# STM32_MCU.net
KiCad netlist of a schematic drawn in Altium Designer
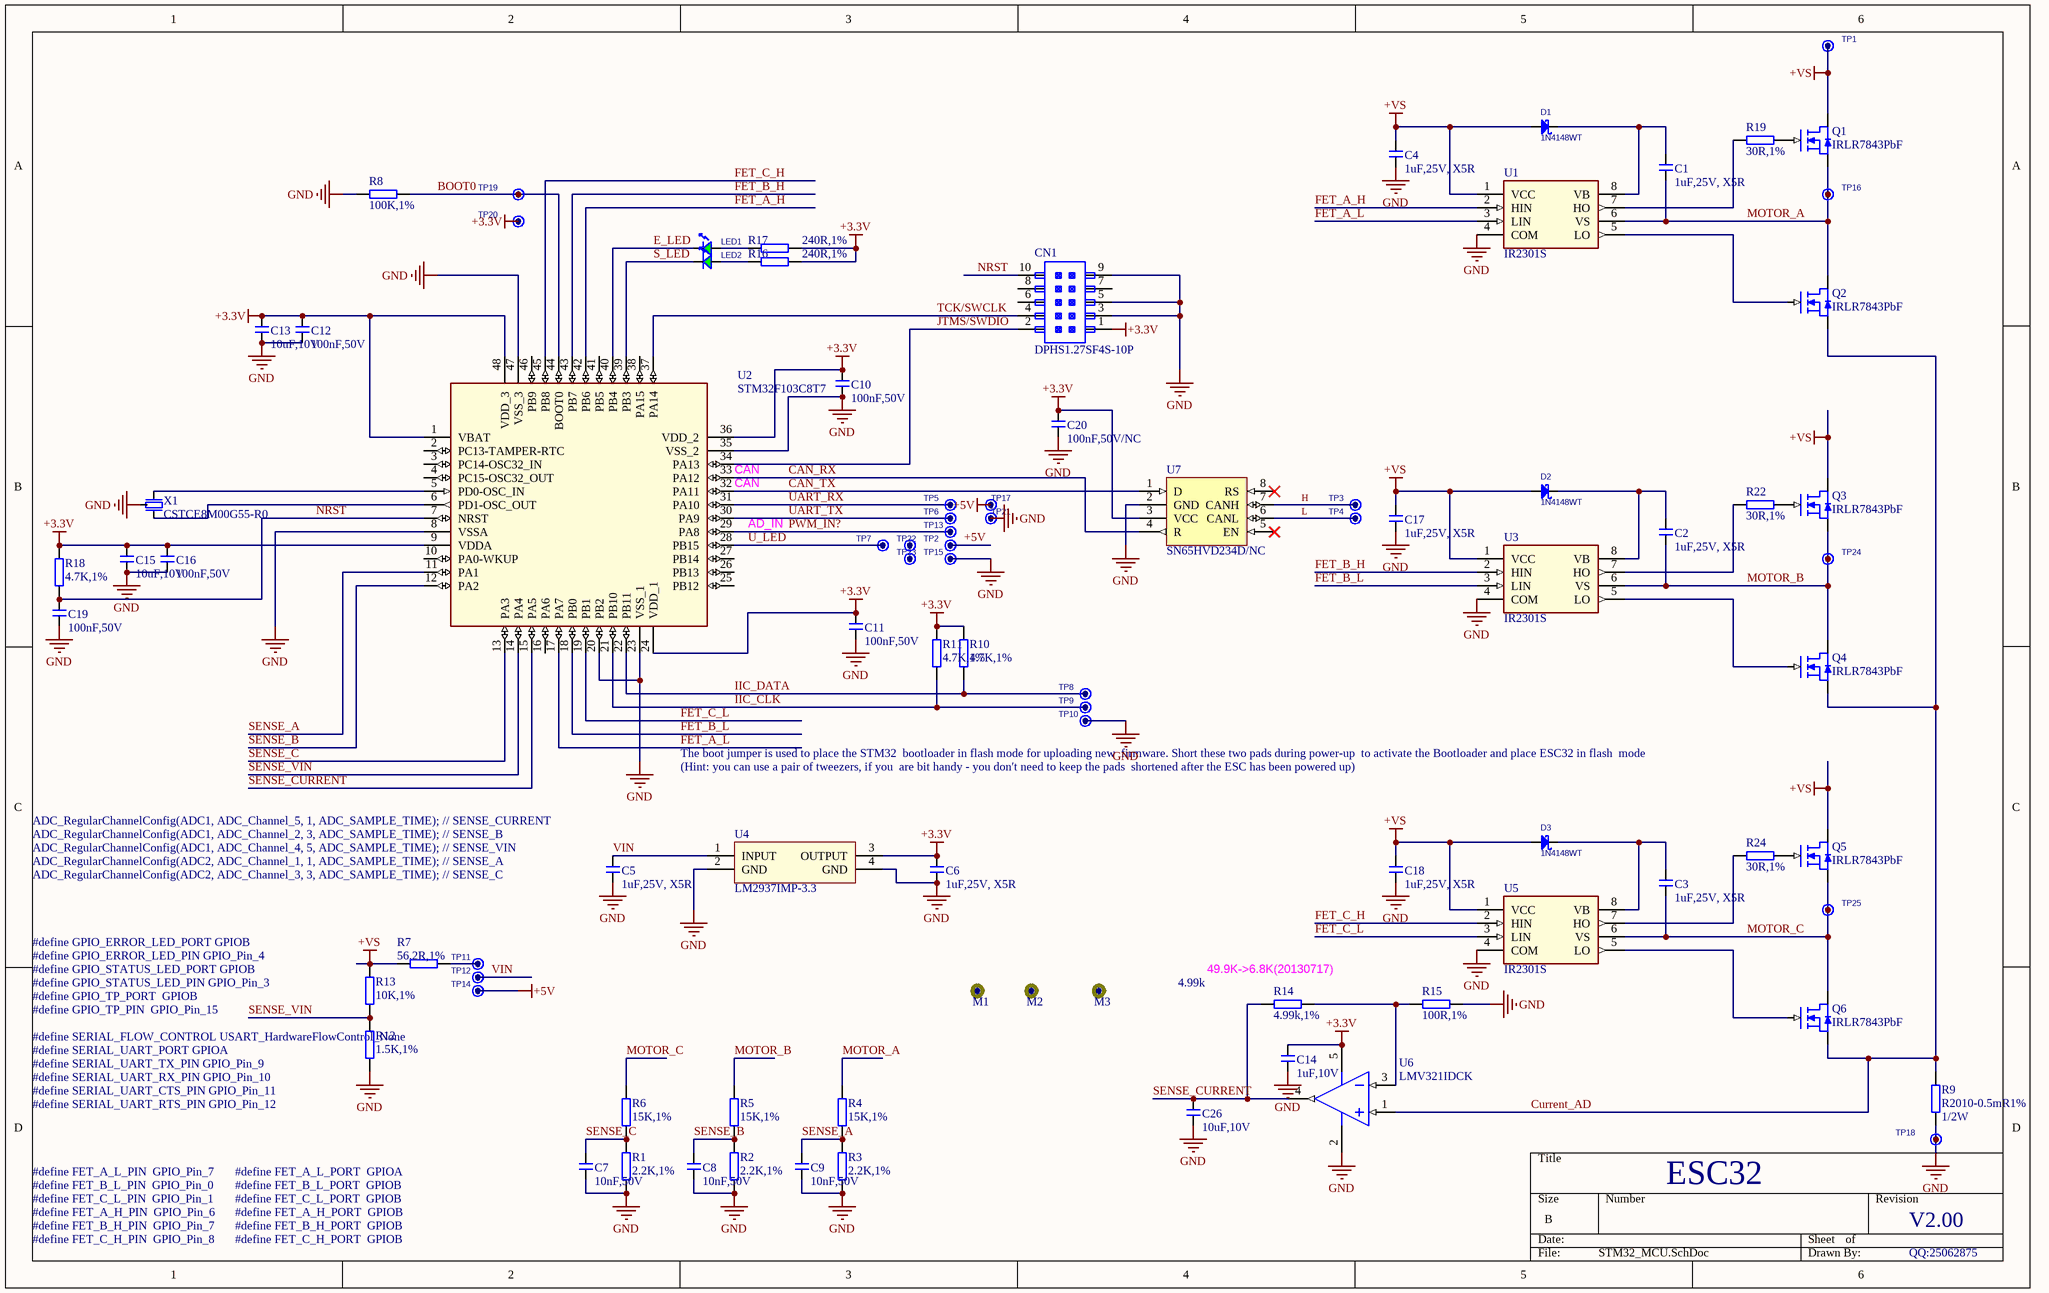
[diagram p0: STM32_MCU.SchDoc]

(export (version "E")
  (design (tool "Eeschema 10.0.6"))
  (components
    (comp (ref "C1")
      (value "1uF,25V, X5R")
      (footprint "CAPC2012L")
      (description "X5R,20%")
      (fields (field (name "Comment") "C0805-1uF/25V"))
      (libsource (lib "cap_n") (part "C0805-1uF/25V"))
    )
    (comp (ref "C2")
      (value "1uF,25V, X5R")
      (footprint "CAPC2012L")
      (description "X5R,20%")
      (fields (field (name "Comment") "C0805-1uF/25V"))
      (libsource (lib "cap_n") (part "C0805-1uF/25V"))
    )
    (comp (ref "C3")
      (value "1uF,25V, X5R")
      (footprint "CAPC2012L")
      (description "X5R,20%")
      (fields (field (name "Comment") "C0805-1uF/25V"))
      (libsource (lib "cap_n") (part "C0805-1uF/25V"))
    )
    (comp (ref "C4")
      (value "1uF,25V, X5R")
      (footprint "CAPC2012L")
      (description "X5R,20%")
      (fields (field (name "Comment") "C0805-1uF/25V"))
      (libsource (lib "cap_n") (part "C0805-1uF/25V"))
    )
    (comp (ref "C5")
      (value "1uF,25V, X5R")
      (footprint "CAPC2012L")
      (description "X5R,20%")
      (fields (field (name "Comment") "C0805-1uF/25V"))
      (libsource (lib "cap_n") (part "C0805-1uF/25V"))
    )
    (comp (ref "C6")
      (value "1uF,25V, X5R")
      (footprint "CAPC2012L")
      (description "X5R,20%")
      (fields (field (name "Comment") "C0805-1uF/25V"))
      (libsource (lib "cap_n") (part "C0805-1uF/25V"))
    )
    (comp (ref "C7")
      (value "10nF,50V")
      (footprint "CAPC1608L")
      (description "X7R")
      (fields (field (name "Comment") "C0603-10nF/50V"))
      (libsource (lib "cap_n") (part "C0603-100nF/50V"))
    )
    (comp (ref "C8")
      (value "10nF,50V")
      (footprint "CAPC1608L")
      (description "X7R")
      (fields (field (name "Comment") "C0603-10nF/50V"))
      (libsource (lib "cap_n") (part "C0603-100nF/50V"))
    )
    (comp (ref "C9")
      (value "10nF,50V")
      (footprint "CAPC1608L")
      (description "X7R")
      (fields (field (name "Comment") "C0603-10nF/50V"))
      (libsource (lib "cap_n") (part "C0603-100nF/50V"))
    )
    (comp (ref "C10")
      (value "100nF,50V")
      (footprint "CAPC1608L")
      (description "X7R")
      (fields (field (name "Comment") "C0603-100nF/50V"))
      (libsource (lib "cap_n") (part "C0603-100nF/50V"))
    )
    (comp (ref "C11")
      (value "100nF,50V")
      (footprint "CAPC1608L")
      (description "X7R")
      (fields (field (name "Comment") "C0603-100nF/50V"))
      (libsource (lib "cap_n") (part "C0603-100nF/50V"))
    )
    (comp (ref "C12")
      (value "100nF,50V")
      (footprint "CAPC1608L")
      (description "X7R")
      (fields (field (name "Comment") "C0603-100nF/50V"))
      (libsource (lib "cap_n") (part "C0603-100nF/50V"))
    )
    (comp (ref "C13")
      (value "10uF,10V")
      (footprint "CAPC1608L")
      (description "X5R,20%")
      (fields (field (name "Comment") "C0603-10uF/10V"))
      (libsource (lib "cap_n") (part "C0603-10uF/10V"))
    )
    (comp (ref "C14")
      (value "1uF,10V")
      (footprint "CAPC1608L")
      (description "X5R,20%")
      (fields (field (name "Comment") "C0603-1uF/10V"))
      (libsource (lib "cap_n") (part "C0603-1uF/10V"))
    )
    (comp (ref "C15")
      (value "10uF,10V")
      (footprint "CAPC1608L")
      (description "X5R,20%")
      (fields (field (name "Comment") "C0603-10uF/10V"))
      (libsource (lib "cap_n") (part "C0603-10uF/10V"))
    )
    (comp (ref "C16")
      (value "100nF,50V")
      (footprint "CAPC1608L")
      (description "X7R")
      (fields (field (name "Comment") "C0603-100nF/50V"))
      (libsource (lib "cap_n") (part "C0603-100nF/50V"))
    )
    (comp (ref "C17")
      (value "1uF,25V, X5R")
      (footprint "CAPC2012L")
      (description "X5R,20%")
      (fields (field (name "Comment") "C0805-1uF/25V"))
      (libsource (lib "cap_n") (part "C0805-1uF/25V"))
    )
    (comp (ref "C18")
      (value "1uF,25V, X5R")
      (footprint "CAPC2012L")
      (description "X5R,20%")
      (fields (field (name "Comment") "C0805-1uF/25V"))
      (libsource (lib "cap_n") (part "C0805-1uF/25V"))
    )
    (comp (ref "C19")
      (value "100nF,50V")
      (footprint "CAPC1608L")
      (description "X7R")
      (fields (field (name "Comment") "C0603-100nF/50V"))
      (libsource (lib "cap_n") (part "C0603-100nF/50V"))
    )
    (comp (ref "C20")
      (value "100nF,50V/NC")
      (footprint "CAPC1608L")
      (description "X7R")
      (fields (field (name "Comment") "C0603-100nF/50V/NC"))
      (libsource (lib "cap_n") (part "C0603-100nF/50V"))
    )
    (comp (ref "C26")
      (value "10uF,10V")
      (footprint "CAPC1608L")
      (description "X7R")
      (fields (field (name "Comment") "C0603-10uF/10V"))
      (libsource (lib "cap_n") (part "C0603-100nF/50V"))
    )
    (comp (ref "CN1")
      (value "DPHS1.27SF4S-10P")
      (footprint "DPHS1.27SF4S-10P")
      (description "1.27 间距表贴双排针, 40芯, PCB板高度为4.3mm")
      (libsource (lib "Connector_STD") (part "DPHS1.27SF4S-10P"))
    )
    (comp (ref "D1")
      (value "1N4148WT")
      (footprint "DIOM1608X06N")
      (description "SURFACE MOUNT FAST SWITCHING DIODE")
      (fields (field (name "MFR") "DIODES"))
      (libsource (lib "Diode_STD") (part "1N4148WT"))
    )
    (comp (ref "D2")
      (value "1N4148WT")
      (footprint "DIOM1608X06N")
      (description "SURFACE MOUNT FAST SWITCHING DIODE")
      (fields (field (name "MFR") "DIODES"))
      (libsource (lib "Diode_STD") (part "1N4148WT"))
    )
    (comp (ref "D3")
      (value "1N4148WT")
      (footprint "DIOM1608X06N")
      (description "SURFACE MOUNT FAST SWITCHING DIODE")
      (fields (field (name "MFR") "DIODES"))
      (libsource (lib "Diode_STD") (part "1N4148WT"))
    )
    (comp (ref "LED1")
      (value "LED-R0603")
      (footprint "LED-G0603")
      (description "LED发光二极管, 绿色, 0603封装")
      (libsource (lib "LEDtube_STD") (part "LED-G0603"))
    )
    (comp (ref "LED2")
      (value "LED-G0603")
      (footprint "LED-G0603")
      (description "LED发光二极管, 绿色, 0603封装")
      (libsource (lib "LEDtube_STD") (part "LED-G0603"))
    )
    (comp (ref "M1")
      (value "MarkPad")
      (footprint "MarkPad")
      (description "mark, 标记芯片和板边位置")
      (libsource (lib "Miscellaneous_STD") (part "MarkPad"))
    )
    (comp (ref "M2")
      (value "MarkPad")
      (footprint "MarkPad")
      (description "mark, 标记芯片和板边位置")
      (libsource (lib "Miscellaneous_STD") (part "MarkPad"))
    )
    (comp (ref "M3")
      (value "MarkPad")
      (footprint "MarkPad")
      (description "mark, 标记芯片和板边位置")
      (libsource (lib "Miscellaneous_STD") (part "MarkPad"))
    )
    (comp (ref "Q1")
      (value "IRLR7843PbF")
      (footprint "TO230P990X239-3N")
      (libsource (lib "MOSFET_STD") (part "IRLR7843PbF"))
    )
    (comp (ref "Q2")
      (value "IRLR7843PbF")
      (footprint "TO230P990X239-3N")
      (libsource (lib "MOSFET_STD") (part "IRLR7843PbF"))
    )
    (comp (ref "Q3")
      (value "IRLR7843PbF")
      (footprint "TO230P990X239-3N")
      (libsource (lib "MOSFET_STD") (part "IRLR7843PbF"))
    )
    (comp (ref "Q4")
      (value "IRLR7843PbF")
      (footprint "TO230P990X239-3N")
      (libsource (lib "MOSFET_STD") (part "IRLR7843PbF"))
    )
    (comp (ref "Q5")
      (value "IRLR7843PbF")
      (footprint "TO230P990X239-3N")
      (libsource (lib "MOSFET_STD") (part "IRLR7843PbF"))
    )
    (comp (ref "Q6")
      (value "IRLR7843PbF")
      (footprint "TO230P990X239-3N")
      (libsource (lib "MOSFET_STD") (part "IRLR7843PbF"))
    )
    (comp (ref "R1")
      (value "2.2K,1%")
      (footprint "RESC1608L")
      (fields (field (name "TOLERANCE") "1%") (field (name "Comment") "R0603-2.2K"))
      (libsource (lib "res") (part "R0603-2.2K"))
    )
    (comp (ref "R2")
      (value "2.2K,1%")
      (footprint "RESC1608L")
      (fields (field (name "TOLERANCE") "1%") (field (name "Comment") "R0603-2.2K"))
      (libsource (lib "res") (part "R0603-2.2K"))
    )
    (comp (ref "R3")
      (value "2.2K,1%")
      (footprint "RESC1608L")
      (fields (field (name "TOLERANCE") "1%") (field (name "Comment") "R0603-2.2K"))
      (libsource (lib "res") (part "R0603-2.2K"))
    )
    (comp (ref "R4")
      (value "15K,1%")
      (footprint "RESC1608L")
      (description "10K,1%")
      (fields (field (name "TOLERANCE") "1%") (field (name "Comment") "R0603-15K"))
      (libsource (lib "res") (part "R0603-10K"))
    )
    (comp (ref "R5")
      (value "15K,1%")
      (footprint "RESC1608L")
      (description "10K,1%")
      (fields (field (name "TOLERANCE") "1%") (field (name "Comment") "R0603-15K"))
      (libsource (lib "res") (part "R0603-10K"))
    )
    (comp (ref "R6")
      (value "15K,1%")
      (footprint "RESC1608L")
      (description "10K,1%")
      (fields (field (name "TOLERANCE") "1%") (field (name "Comment") "R0603-15K"))
      (libsource (lib "res") (part "R0603-10K"))
    )
    (comp (ref "R7")
      (value "56.2R,1%")
      (footprint "RESC2012L")
      (fields (field (name "Comment") "R0805-56.2R"))
      (libsource (lib "res") (part "R0805-56.2R"))
    )
    (comp (ref "R8")
      (value "100K,1%")
      (footprint "RESC1608L")
      (fields (field (name "TOLERANCE") "1%") (field (name "Comment") "R0603-100K"))
      (libsource (lib "res") (part "R0603-100K"))
    )
    (comp (ref "R9")
      (value "R2010-0.5mR1%")
      (footprint "RC2010-5025X07N")
      (description "Vishay WSL功率型电阻")
      (fields (field (name "功?") "1/2W"))
      (libsource (lib "Resistance_STD") (part "R2010-0.22R1%"))
    )
    (comp (ref "R10")
      (value "4.7K,1%")
      (footprint "RESC1608L")
      (fields (field (name "TOLERANCE") "1%") (field (name "Comment") "R0603-4.7K"))
      (libsource (lib "res") (part "R0603-4.7K"))
    )
    (comp (ref "R11")
      (value "4.7K,1%")
      (footprint "RESC1608L")
      (fields (field (name "TOLERANCE") "1%") (field (name "Comment") "R0603-4.7K"))
      (libsource (lib "res") (part "R0603-4.7K"))
    )
    (comp (ref "R12")
      (value "1.5K,1%")
      (footprint "RESC1608L")
      (description "15K,1%")
      (fields (field (name "TOLERANCE") "1%") (field (name "Comment") "R0603-1.5K"))
      (libsource (lib "res") (part "R0603-15K"))
    )
    (comp (ref "R13")
      (value "10K,1%")
      (footprint "RESC1608L")
      (description "100K,1%")
      (fields (field (name "TOLERANCE") "1%") (field (name "Comment") "R0603-10K"))
      (libsource (lib "res") (part "R0603-100K"))
    )
    (comp (ref "R14")
      (value "4.99k,1%")
      (footprint "RESC1608L")
      (fields (field (name "TOLERANCE") "1%") (field (name "Comment") "R0603-4.99k"))
      (libsource (lib "res") (part "R0603-49.9K"))
    )
    (comp (ref "R15")
      (value "100R,1%")
      (footprint "RESC1608L")
      (fields (field (name "TOLERANCE") "1%") (field (name "Comment") "R0603-100R"))
      (libsource (lib "res") (part "R0603-100R"))
    )
    (comp (ref "R16")
      (value "240R,1%")
      (footprint "RESC1608L")
      (fields (field (name "TOLERANCE") "1%") (field (name "Comment") "R0603-240R"))
      (libsource (lib "res") (part "R0603-240R"))
    )
    (comp (ref "R17")
      (value "240R,1%")
      (footprint "RESC1608L")
      (fields (field (name "TOLERANCE") "1%") (field (name "Comment") "R0603-240R"))
      (libsource (lib "res") (part "R0603-240R"))
    )
    (comp (ref "R18")
      (value "4.7K,1%")
      (footprint "RESC1608L")
      (fields (field (name "TOLERANCE") "1%") (field (name "Comment") "R0603-4.7K"))
      (libsource (lib "res") (part "R0603-4.7K"))
    )
    (comp (ref "R19")
      (value "30R,1%")
      (footprint "RESC1608L")
      (description "22R,1%")
      (fields (field (name "TOLERANCE") "1%") (field (name "Comment") "R0603-30R"))
      (libsource (lib "res") (part "R0603-22R"))
    )
    (comp (ref "R22")
      (value "30R,1%")
      (footprint "RESC1608L")
      (description "22R,1%")
      (fields (field (name "TOLERANCE") "1%") (field (name "Comment") "R0603-30R"))
      (libsource (lib "res") (part "R0603-22R"))
    )
    (comp (ref "R24")
      (value "30R,1%")
      (footprint "RESC1608L")
      (description "22R,1%")
      (fields (field (name "TOLERANCE") "1%") (field (name "Comment") "R0603-30R"))
      (libsource (lib "res") (part "R0603-22R"))
    )
    (comp (ref "TP1")
      (value "TPS50mil")
      (footprint "TP3")
      (description "Test Point, 12x25mil, Not Populated")
      (libsource (lib "mis") (part "TPS50mil"))
    )
    (comp (ref "TP2")
      (value "TPS50mil")
      (footprint "TPS1.5mm")
      (description "Test Point, 12x25mil, Not Populated")
      (libsource (lib "mis") (part "TPS50mil"))
    )
    (comp (ref "TP3")
      (value "TPS50mil")
      (footprint "TPS1.5mm")
      (description "Test Point, 12x25mil, Not Populated")
      (libsource (lib "mis") (part "TPS50mil"))
    )
    (comp (ref "TP4")
      (value "TPS50mil")
      (footprint "TPS1.5mm")
      (description "Test Point, 12x25mil, Not Populated")
      (libsource (lib "mis") (part "TPS50mil"))
    )
    (comp (ref "TP5")
      (value "TPS50mil")
      (footprint "TPS1.5mm")
      (description "Test Point, 12x25mil, Not Populated")
      (libsource (lib "mis") (part "TPS50mil"))
    )
    (comp (ref "TP6")
      (value "TPS50mil")
      (footprint "TPS1.5mm")
      (description "Test Point, 12x25mil, Not Populated")
      (libsource (lib "mis") (part "TPS50mil"))
    )
    (comp (ref "TP7")
      (value "TPS50mil")
      (footprint "TPS1.5mm")
      (description "Test Point, 12x25mil, Not Populated")
      (libsource (lib "mis") (part "TPS50mil"))
    )
    (comp (ref "TP8")
      (value "TPS50mil")
      (footprint "TPS1.5mm")
      (description "Test Point, 12x25mil, Not Populated")
      (libsource (lib "mis") (part "TPS50mil"))
    )
    (comp (ref "TP9")
      (value "TPS50mil")
      (footprint "TPS1.5mm")
      (description "Test Point, 12x25mil, Not Populated")
      (libsource (lib "mis") (part "TPS50mil"))
    )
    (comp (ref "TP10")
      (value "TPS50mil")
      (footprint "TPS1.5mm")
      (description "Test Point, 12x25mil, Not Populated")
      (libsource (lib "mis") (part "TPS50mil"))
    )
    (comp (ref "TP11")
      (value "TPS50mil")
      (footprint "TP1")
      (description "Test Point, 12x25mil, Not Populated")
      (libsource (lib "mis") (part "TPS50mil"))
    )
    (comp (ref "TP12")
      (value "TPS50mil")
      (footprint "TP2")
      (description "Test Point, 12x25mil, Not Populated")
      (libsource (lib "mis") (part "TPS50mil"))
    )
    (comp (ref "TP13")
      (value "TPS50mil")
      (footprint "TPS1.5mm")
      (description "Test Point, 12x25mil, Not Populated")
      (libsource (lib "mis") (part "TPS50mil"))
    )
    (comp (ref "TP14")
      (value "TPS50mil")
      (footprint "TP1")
      (description "Test Point, 12x25mil, Not Populated")
      (libsource (lib "mis") (part "TPS50mil"))
    )
    (comp (ref "TP15")
      (value "TPS50mil")
      (footprint "TPS1.5mm")
      (description "Test Point, 12x25mil, Not Populated")
      (libsource (lib "mis") (part "TPS50mil"))
    )
    (comp (ref "TP16")
      (value "TPS50mil")
      (footprint "TP3")
      (description "Test Point, 12x25mil, Not Populated")
      (libsource (lib "mis") (part "TPS50mil"))
    )
    (comp (ref "TP17")
      (value "TPS50mil")
      (footprint "TPS1.5mm")
      (description "Test Point, 12x25mil, Not Populated")
      (libsource (lib "mis") (part "TPS50mil"))
    )
    (comp (ref "TP18")
      (value "TPS50mil")
      (footprint "TP3")
      (description "Test Point, 12x25mil, Not Populated")
      (libsource (lib "mis") (part "TPS50mil"))
    )
    (comp (ref "TP19")
      (value "TPS50mil")
      (footprint "TPS1.5mm")
      (description "Test Point, 12x25mil, Not Populated")
      (libsource (lib "mis") (part "TPS50mil"))
    )
    (comp (ref "TP20")
      (value "TPS50mil")
      (footprint "TPS1.5mm")
      (description "Test Point, 12x25mil, Not Populated")
      (libsource (lib "mis") (part "TPS50mil"))
    )
    (comp (ref "TP21")
      (value "TPS50mil")
      (footprint "TPS1.5mm")
      (description "Test Point, 12x25mil, Not Populated")
      (libsource (lib "mis") (part "TPS50mil"))
    )
    (comp (ref "TP22")
      (value "TPS50mil")
      (footprint "TPS1.5mm")
      (description "Test Point, 12x25mil, Not Populated")
      (libsource (lib "mis") (part "TPS50mil"))
    )
    (comp (ref "TP23")
      (value "TPS50mil")
      (footprint "TPS1.5mm")
      (description "Test Point, 12x25mil, Not Populated")
      (libsource (lib "mis") (part "TPS50mil"))
    )
    (comp (ref "TP24")
      (value "TPS50mil")
      (footprint "TP3")
      (description "Test Point, 12x25mil, Not Populated")
      (libsource (lib "mis") (part "TPS50mil"))
    )
    (comp (ref "TP25")
      (value "TPS50mil")
      (footprint "TP3")
      (description "Test Point, 12x25mil, Not Populated")
      (libsource (lib "mis") (part "TPS50mil"))
    )
    (comp (ref "U1")
      (value "IR2301S")
      (footprint "SOIC127P600X175-8L")
      (libsource (lib "MOSFET_STD") (part "IR2301S"))
    )
    (comp (ref "U2")
      (value "STM32F103C8T7")
      (footprint "TSQFP50P900X900X160-48L")
      (libsource (lib "MCU_STD") (part "STM32F103C8T7"))
    )
    (comp (ref "U3")
      (value "IR2301S")
      (footprint "SOIC127P600X175-8L")
      (libsource (lib "MOSFET_STD") (part "IR2301S"))
    )
    (comp (ref "U4")
      (value "LM2937IMP-3.3")
      (footprint "SOT230P700X180-4N")
      (libsource (lib "temp") (part "LM2937IMP-3.3"))
    )
    (comp (ref "U5")
      (value "IR2301S")
      (footprint "SOIC127P600X175-8L")
      (libsource (lib "MOSFET_STD") (part "IR2301S"))
    )
    (comp (ref "U6")
      (value "LMV321IDCK")
      (footprint "SOT65P210X110-5L(SC70)")
      (libsource (lib "Analog_STD") (part "LMV321IDCK"))
    )
    (comp (ref "U7")
      (value "SN65HVD234D/NC")
      (footprint "SOIC127P600X175-8M")
      (description "3.3-V CAN TRANSCEIVERS")
      (libsource (lib "Interface_STD") (part "SN65HVD234D"))
    )
    (comp (ref "X1")
      (value "CSTCE8M00G55-R0")
      (footprint "CSTCE_G")
      (libsource (lib "Crystal_STD") (part "CSTCE8M00G55-R0"))
    )
  )
  (nets
    (net (code "1") (name "+3.3V") (class "Default")
      (node (ref "C10") (pin "1") (pintype "passive"))
      (node (ref "C11") (pin "1") (pintype "passive"))
      (node (ref "C12") (pin "1") (pintype "passive"))
      (node (ref "C13") (pin "1") (pintype "passive"))
      (node (ref "C14") (pin "1") (pintype "passive"))
      (node (ref "C15") (pin "1") (pintype "passive"))
      (node (ref "C16") (pin "1") (pintype "passive"))
      (node (ref "C20") (pin "1") (pintype "passive"))
      (node (ref "C6") (pin "1") (pintype "passive"))
      (node (ref "CN1") (pin "1") (pinfunction "1_1") (pintype "passive"))
      (node (ref "R10") (pin "2") (pintype "passive"))
      (node (ref "R11") (pin "2") (pintype "passive"))
      (node (ref "R16") (pin "2") (pintype "passive"))
      (node (ref "R17") (pin "2") (pintype "passive"))
      (node (ref "R18") (pin "2") (pintype "passive"))
      (node (ref "TP20") (pin "1") (pinfunction "1_1") (pintype "passive"))
      (node (ref "U2") (pin "1") (pinfunction "VBAT_1") (pintype "power_in"))
      (node (ref "U2") (pin "24") (pinfunction "VDD_1_24") (pintype "power_in"))
      (node (ref "U2") (pin "36") (pinfunction "VDD_2_36") (pintype "power_in"))
      (node (ref "U2") (pin "48") (pinfunction "VDD_3_48") (pintype "power_in"))
      (node (ref "U2") (pin "9") (pinfunction "VDDA_9") (pintype "power_in"))
      (node (ref "U4") (pin "3") (pinfunction "OUTPUT_3") (pintype "power_in"))
      (node (ref "U6") (pin "5") (pinfunction "V+_5") (pintype "power_in"))
      (node (ref "U7") (pin "3") (pinfunction "VCC_3") (pintype "power_in"))
    )
    (net (code "2") (name "+5V") (class "Default")
      (node (ref "TP14") (pin "1") (pinfunction "1_1") (pintype "passive"))
      (node (ref "TP17") (pin "1") (pinfunction "1_1") (pintype "passive"))
      (node (ref "TP2") (pin "1") (pinfunction "1_1") (pintype "passive"))
    )
    (net (code "3") (name "+VS") (class "Default")
      (node (ref "C17") (pin "1") (pintype "passive"))
      (node (ref "C18") (pin "1") (pintype "passive"))
      (node (ref "C4") (pin "1") (pintype "passive"))
      (node (ref "D1") (pin "1") (pinfunction "A_1") (pintype "passive"))
      (node (ref "D2") (pin "1") (pinfunction "A_1") (pintype "passive"))
      (node (ref "D3") (pin "1") (pinfunction "A_1") (pintype "passive"))
      (node (ref "Q1") (pin "4") (pinfunction "D_4") (pintype "power_in"))
      (node (ref "Q3") (pin "4") (pinfunction "D_4") (pintype "power_in"))
      (node (ref "Q5") (pin "4") (pinfunction "D_4") (pintype "power_in"))
      (node (ref "R13") (pin "2") (pintype "passive"))
      (node (ref "R7") (pin "2") (pintype "passive"))
      (node (ref "TP1") (pin "1") (pinfunction "1_1") (pintype "passive"))
      (node (ref "U1") (pin "1") (pinfunction "VCC_1") (pintype "power_in"))
      (node (ref "U3") (pin "1") (pinfunction "VCC_1") (pintype "power_in"))
      (node (ref "U5") (pin "1") (pinfunction "VCC_1") (pintype "power_in"))
    )
    (net (code "4") (name "/BOOT0") (class "Default")
      (node (ref "R8") (pin "1") (pintype "passive"))
      (node (ref "TP19") (pin "1") (pinfunction "1_1") (pintype "passive"))
      (node (ref "U2") (pin "44") (pinfunction "BOOT0_44") (pintype "bidirectional"))
    )
    (net (code "5") (name "/CAN_RX") (class "Default")
      (node (ref "U2") (pin "33") (pinfunction "PA12_33") (pintype "bidirectional"))
      (node (ref "U7") (pin "4") (pinfunction "R_4") (pintype "output"))
    )
    (net (code "6") (name "/CAN_TX") (class "Default")
      (node (ref "U2") (pin "32") (pinfunction "PA11_32") (pintype "bidirectional"))
      (node (ref "U7") (pin "1") (pinfunction "D_1") (pintype "input"))
    )
    (net (code "7") (name "/Current_AD") (class "Default")
      (node (ref "Q2") (pin "3") (pinfunction "S_3") (pintype "power_in"))
      (node (ref "Q4") (pin "3") (pinfunction "S_3") (pintype "power_in"))
      (node (ref "Q6") (pin "3") (pinfunction "S_3") (pintype "power_in"))
      (node (ref "R9") (pin "2") (pintype "passive"))
      (node (ref "U6") (pin "1") (pinfunction "IN1+_1") (pintype "input"))
    )
    (net (code "8") (name "/E_LED") (class "Default")
      (node (ref "LED1") (pin "2") (pinfunction "K_2") (pintype "passive"))
      (node (ref "U2") (pin "40") (pinfunction "PB4_40") (pintype "bidirectional"))
    )
    (net (code "9") (name "/FET_A_H") (class "Default")
      (node (ref "U1") (pin "2") (pinfunction "HIN_2") (pintype "input"))
      (node (ref "U2") (pin "42") (pinfunction "PB6_42") (pintype "bidirectional"))
    )
    (net (code "10") (name "/FET_A_L") (class "Default")
      (node (ref "U1") (pin "3") (pinfunction "LIN_3") (pintype "input"))
      (node (ref "U2") (pin "17") (pinfunction "PA7_17") (pintype "bidirectional"))
    )
    (net (code "11") (name "/FET_B_H") (class "Default")
      (node (ref "U2") (pin "43") (pinfunction "PB7_43") (pintype "bidirectional"))
      (node (ref "U3") (pin "2") (pinfunction "HIN_2") (pintype "input"))
    )
    (net (code "12") (name "/FET_B_L") (class "Default")
      (node (ref "U2") (pin "18") (pinfunction "PB0_18") (pintype "bidirectional"))
      (node (ref "U3") (pin "3") (pinfunction "LIN_3") (pintype "input"))
    )
    (net (code "13") (name "/FET_C_H") (class "Default")
      (node (ref "U2") (pin "45") (pinfunction "PB8_45") (pintype "bidirectional"))
      (node (ref "U5") (pin "2") (pinfunction "HIN_2") (pintype "input"))
    )
    (net (code "14") (name "/FET_C_L") (class "Default")
      (node (ref "U2") (pin "19") (pinfunction "PB1_19") (pintype "bidirectional"))
      (node (ref "U5") (pin "3") (pinfunction "LIN_3") (pintype "input"))
    )
    (net (code "15") (name "/H") (class "Default")
      (node (ref "TP3") (pin "1") (pinfunction "1_1") (pintype "passive"))
      (node (ref "U7") (pin "7") (pinfunction "CANH_7") (pintype "bidirectional"))
    )
    (net (code "16") (name "/IIC_CLK") (class "Default")
      (node (ref "R11") (pin "1") (pintype "passive"))
      (node (ref "TP9") (pin "1") (pinfunction "1_1") (pintype "passive"))
      (node (ref "U2") (pin "21") (pinfunction "PB10_21") (pintype "bidirectional"))
    )
    (net (code "17") (name "/IIC_DATA") (class "Default")
      (node (ref "R10") (pin "1") (pintype "passive"))
      (node (ref "TP8") (pin "1") (pinfunction "1_1") (pintype "passive"))
      (node (ref "U2") (pin "22") (pinfunction "PB11_22") (pintype "bidirectional"))
    )
    (net (code "18") (name "/JTMS{slash}SWDIO") (class "Default")
      (node (ref "CN1") (pin "2") (pinfunction "2_2") (pintype "passive"))
      (node (ref "U2") (pin "34") (pinfunction "PA13_34") (pintype "bidirectional"))
    )
    (net (code "19") (name "/L") (class "Default")
      (node (ref "TP4") (pin "1") (pinfunction "1_1") (pintype "passive"))
      (node (ref "U7") (pin "6") (pinfunction "CANL_6") (pintype "bidirectional"))
    )
    (net (code "20") (name "/MOTOR_A") (class "Default")
      (node (ref "C1") (pin "2") (pintype "passive"))
      (node (ref "Q1") (pin "3") (pinfunction "S_3") (pintype "power_in"))
      (node (ref "Q2") (pin "4") (pinfunction "D_4") (pintype "power_in"))
      (node (ref "R4") (pin "2") (pintype "passive"))
      (node (ref "TP16") (pin "1") (pinfunction "1_1") (pintype "passive"))
      (node (ref "U1") (pin "6") (pinfunction "VS_6") (pintype "power_in"))
    )
    (net (code "21") (name "/MOTOR_B") (class "Default")
      (node (ref "C2") (pin "2") (pintype "passive"))
      (node (ref "Q3") (pin "3") (pinfunction "S_3") (pintype "power_in"))
      (node (ref "Q4") (pin "4") (pinfunction "D_4") (pintype "power_in"))
      (node (ref "R5") (pin "2") (pintype "passive"))
      (node (ref "TP24") (pin "1") (pinfunction "1_1") (pintype "passive"))
      (node (ref "U3") (pin "6") (pinfunction "VS_6") (pintype "power_in"))
    )
    (net (code "22") (name "/MOTOR_C") (class "Default")
      (node (ref "C3") (pin "2") (pintype "passive"))
      (node (ref "Q5") (pin "3") (pinfunction "S_3") (pintype "power_in"))
      (node (ref "Q6") (pin "4") (pinfunction "D_4") (pintype "power_in"))
      (node (ref "R6") (pin "2") (pintype "passive"))
      (node (ref "TP25") (pin "1") (pinfunction "1_1") (pintype "passive"))
      (node (ref "U5") (pin "6") (pinfunction "VS_6") (pintype "power_in"))
    )
    (net (code "23") (name "/NRST") (class "Default")
      (node (ref "C19") (pin "1") (pintype "passive"))
      (node (ref "CN1") (pin "10") (pinfunction "6_10") (pintype "passive"))
      (node (ref "R18") (pin "1") (pintype "passive"))
      (node (ref "U2") (pin "7") (pinfunction "NRST_7") (pintype "bidirectional"))
    )
    (net (code "24") (name "/PWM_IN?") (class "Default")
      (node (ref "TP13") (pin "1") (pinfunction "1_1") (pintype "passive"))
      (node (ref "U2") (pin "29") (pinfunction "PA8_29") (pintype "bidirectional"))
    )
    (net (code "25") (name "/SENSE_A") (class "Default")
      (node (ref "C9") (pin "1") (pintype "passive"))
      (node (ref "R3") (pin "2") (pintype "passive"))
      (node (ref "R4") (pin "1") (pintype "passive"))
      (node (ref "U2") (pin "11") (pinfunction "PA1_11") (pintype "bidirectional"))
    )
    (net (code "26") (name "/SENSE_B") (class "Default")
      (node (ref "C8") (pin "1") (pintype "passive"))
      (node (ref "R2") (pin "2") (pintype "passive"))
      (node (ref "R5") (pin "1") (pintype "passive"))
      (node (ref "U2") (pin "12") (pinfunction "PA2_12") (pintype "bidirectional"))
    )
    (net (code "27") (name "/SENSE_C") (class "Default")
      (node (ref "C7") (pin "1") (pintype "passive"))
      (node (ref "R1") (pin "2") (pintype "passive"))
      (node (ref "R6") (pin "1") (pintype "passive"))
      (node (ref "U2") (pin "13") (pinfunction "PA3_13") (pintype "bidirectional"))
    )
    (net (code "28") (name "/SENSE_CURRENT") (class "Default")
      (node (ref "C26") (pin "1") (pintype "passive"))
      (node (ref "R14") (pin "2") (pintype "passive"))
      (node (ref "U2") (pin "15") (pinfunction "PA5_15") (pintype "bidirectional"))
      (node (ref "U6") (pin "4") (pinfunction "OUT1_4") (pintype "output"))
    )
    (net (code "29") (name "/SENSE_VIN") (class "Default")
      (node (ref "R12") (pin "2") (pintype "passive"))
      (node (ref "R13") (pin "1") (pintype "passive"))
      (node (ref "U2") (pin "14") (pinfunction "PA4_14") (pintype "bidirectional"))
    )
    (net (code "30") (name "/S_LED") (class "Default")
      (node (ref "LED2") (pin "2") (pinfunction "K_2") (pintype "passive"))
      (node (ref "U2") (pin "39") (pinfunction "PB3_39") (pintype "bidirectional"))
    )
    (net (code "31") (name "/TCK{slash}SWCLK") (class "Default")
      (node (ref "CN1") (pin "4") (pinfunction "4_4") (pintype "passive"))
      (node (ref "U2") (pin "37") (pinfunction "PA14_37") (pintype "bidirectional"))
    )
    (net (code "32") (name "/UART_RX") (class "Default")
      (node (ref "TP5") (pin "1") (pinfunction "1_1") (pintype "passive"))
      (node (ref "U2") (pin "31") (pinfunction "PA10_31") (pintype "bidirectional"))
    )
    (net (code "33") (name "/UART_TX") (class "Default")
      (node (ref "TP6") (pin "1") (pinfunction "1_1") (pintype "passive"))
      (node (ref "U2") (pin "30") (pinfunction "PA9_30") (pintype "bidirectional"))
    )
    (net (code "34") (name "/U_LED") (class "Default")
      (node (ref "TP7") (pin "1") (pinfunction "1_1") (pintype "passive"))
      (node (ref "U2") (pin "28") (pinfunction "PB15_28") (pintype "bidirectional"))
    )
    (net (code "35") (name "/VIN") (class "Default")
      (node (ref "C5") (pin "1") (pintype "passive"))
      (node (ref "TP12") (pin "1") (pinfunction "1_1") (pintype "passive"))
      (node (ref "U4") (pin "1") (pinfunction "INPUT_1") (pintype "power_in"))
    )
    (net (code "36") (name "GND") (class "Default")
      (node (ref "C10") (pin "2") (pintype "passive"))
      (node (ref "C11") (pin "2") (pintype "passive"))
      (node (ref "C12") (pin "2") (pintype "passive"))
      (node (ref "C13") (pin "2") (pintype "passive"))
      (node (ref "C14") (pin "2") (pintype "passive"))
      (node (ref "C15") (pin "2") (pintype "passive"))
      (node (ref "C16") (pin "2") (pintype "passive"))
      (node (ref "C17") (pin "2") (pintype "passive"))
      (node (ref "C18") (pin "2") (pintype "passive"))
      (node (ref "C19") (pin "2") (pintype "passive"))
      (node (ref "C20") (pin "2") (pintype "passive"))
      (node (ref "C26") (pin "2") (pintype "passive"))
      (node (ref "C4") (pin "2") (pintype "passive"))
      (node (ref "C5") (pin "2") (pintype "passive"))
      (node (ref "C6") (pin "2") (pintype "passive"))
      (node (ref "C7") (pin "2") (pintype "passive"))
      (node (ref "C8") (pin "2") (pintype "passive"))
      (node (ref "C9") (pin "2") (pintype "passive"))
      (node (ref "CN1") (pin "3") (pinfunction "3_3") (pintype "passive"))
      (node (ref "CN1") (pin "5") (pinfunction "5_5") (pintype "passive"))
      (node (ref "CN1") (pin "9") (pinfunction "7_9") (pintype "passive"))
      (node (ref "R1") (pin "1") (pintype "passive"))
      (node (ref "R12") (pin "1") (pintype "passive"))
      (node (ref "R15") (pin "1") (pintype "passive"))
      (node (ref "R2") (pin "1") (pintype "passive"))
      (node (ref "R3") (pin "1") (pintype "passive"))
      (node (ref "R8") (pin "2") (pintype "passive"))
      (node (ref "R9") (pin "1") (pintype "passive"))
      (node (ref "TP10") (pin "1") (pinfunction "1_1") (pintype "passive"))
      (node (ref "TP15") (pin "1") (pinfunction "1_1") (pintype "passive"))
      (node (ref "TP18") (pin "1") (pinfunction "1_1") (pintype "passive"))
      (node (ref "TP21") (pin "1") (pinfunction "1_1") (pintype "passive"))
      (node (ref "U1") (pin "4") (pinfunction "COM_4") (pintype "power_in"))
      (node (ref "U2") (pin "20") (pinfunction "PB2_20") (pintype "bidirectional"))
      (node (ref "U2") (pin "23") (pinfunction "VSS_1_23") (pintype "power_in"))
      (node (ref "U2") (pin "35") (pinfunction "VSS_2_35") (pintype "power_in"))
      (node (ref "U2") (pin "47") (pinfunction "VSS_3_47") (pintype "power_in"))
      (node (ref "U2") (pin "8") (pinfunction "VSSA_8") (pintype "power_in"))
      (node (ref "U3") (pin "4") (pinfunction "COM_4") (pintype "power_in"))
      (node (ref "U4") (pin "2") (pinfunction "GND_2") (pintype "power_in"))
      (node (ref "U4") (pin "4") (pinfunction "GND_4") (pintype "power_in"))
      (node (ref "U5") (pin "4") (pinfunction "COM_4") (pintype "power_in"))
      (node (ref "U6") (pin "2") (pinfunction "GND_2") (pintype "power_in"))
      (node (ref "U7") (pin "2") (pinfunction "GND_2") (pintype "power_in"))
      (node (ref "X1") (pin "2") (pinfunction "GND_2") (pintype "passive"))
    )
    (net (code "37") (name "Net-(D1-K)") (class "Default")
      (node (ref "C1") (pin "1") (pintype "passive"))
      (node (ref "D1") (pin "2") (pinfunction "K_2") (pintype "passive"))
      (node (ref "U1") (pin "8") (pinfunction "VB_8") (pintype "power_in"))
    )
    (net (code "38") (name "Net-(D2-K)") (class "Default")
      (node (ref "C2") (pin "1") (pintype "passive"))
      (node (ref "D2") (pin "2") (pinfunction "K_2") (pintype "passive"))
      (node (ref "U3") (pin "8") (pinfunction "VB_8") (pintype "power_in"))
    )
    (net (code "39") (name "Net-(D3-K)") (class "Default")
      (node (ref "C3") (pin "1") (pintype "passive"))
      (node (ref "D3") (pin "2") (pinfunction "K_2") (pintype "passive"))
      (node (ref "U5") (pin "8") (pinfunction "VB_8") (pintype "power_in"))
    )
    (net (code "40") (name "Net-(LED1-A)") (class "Default")
      (node (ref "LED1") (pin "1") (pinfunction "A_1") (pintype "passive"))
      (node (ref "R17") (pin "1") (pintype "passive"))
    )
    (net (code "41") (name "Net-(LED2-A)") (class "Default")
      (node (ref "LED2") (pin "1") (pinfunction "A_1") (pintype "passive"))
      (node (ref "R16") (pin "1") (pintype "passive"))
    )
    (net (code "42") (name "Net-(Q1-G)") (class "Default")
      (node (ref "Q1") (pin "1") (pinfunction "G_1") (pintype "input"))
      (node (ref "R19") (pin "2") (pintype "passive"))
    )
    (net (code "43") (name "Net-(Q2-G)") (class "Default")
      (node (ref "Q2") (pin "1") (pinfunction "G_1") (pintype "input"))
      (node (ref "U1") (pin "5") (pinfunction "LO_5") (pintype "output"))
    )
    (net (code "44") (name "Net-(Q3-G)") (class "Default")
      (node (ref "Q3") (pin "1") (pinfunction "G_1") (pintype "input"))
      (node (ref "R22") (pin "2") (pintype "passive"))
    )
    (net (code "45") (name "Net-(Q4-G)") (class "Default")
      (node (ref "Q4") (pin "1") (pinfunction "G_1") (pintype "input"))
      (node (ref "U3") (pin "5") (pinfunction "LO_5") (pintype "output"))
    )
    (net (code "46") (name "Net-(Q5-G)") (class "Default")
      (node (ref "Q5") (pin "1") (pinfunction "G_1") (pintype "input"))
      (node (ref "R24") (pin "2") (pintype "passive"))
    )
    (net (code "47") (name "Net-(Q6-G)") (class "Default")
      (node (ref "Q6") (pin "1") (pinfunction "G_1") (pintype "input"))
      (node (ref "U5") (pin "5") (pinfunction "LO_5") (pintype "output"))
    )
    (net (code "48") (name "Net-(R7-Pad1)") (class "Default")
      (node (ref "R7") (pin "1") (pintype "passive"))
      (node (ref "TP11") (pin "1") (pinfunction "1_1") (pintype "passive"))
    )
    (net (code "49") (name "Net-(U1-HO)") (class "Default")
      (node (ref "R19") (pin "1") (pintype "passive"))
      (node (ref "U1") (pin "7") (pinfunction "HO_7") (pintype "output"))
    )
    (net (code "50") (name "Net-(U2-PD0-OSC_IN)") (class "Default")
      (node (ref "U2") (pin "5") (pinfunction "PD0-OSC_IN_5") (pintype "input"))
      (node (ref "X1") (pin "1") (pinfunction "1_1") (pintype "passive"))
    )
    (net (code "51") (name "Net-(U2-PD1-OSC_OUT)") (class "Default")
      (node (ref "U2") (pin "6") (pinfunction "PD1-OSC_OUT_6") (pintype "output"))
      (node (ref "X1") (pin "3") (pinfunction "3_3") (pintype "passive"))
    )
    (net (code "52") (name "Net-(U3-HO)") (class "Default")
      (node (ref "R22") (pin "1") (pintype "passive"))
      (node (ref "U3") (pin "7") (pinfunction "HO_7") (pintype "output"))
    )
    (net (code "53") (name "Net-(U5-HO)") (class "Default")
      (node (ref "R24") (pin "1") (pintype "passive"))
      (node (ref "U5") (pin "7") (pinfunction "HO_7") (pintype "output"))
    )
    (net (code "54") (name "Net-(U6-IN1-)") (class "Default")
      (node (ref "R14") (pin "1") (pintype "passive"))
      (node (ref "R15") (pin "2") (pintype "passive"))
      (node (ref "U6") (pin "3") (pinfunction "IN1-_3") (pintype "input"))
    )
    (net (code "55") (name "unconnected-(CN1-Pad6)") (class "Default")
      (node (ref "CN1") (pin "6") (pinfunction "6_6") (pintype "passive"))
    )
    (net (code "56") (name "unconnected-(CN1-Pad7)") (class "Default")
      (node (ref "CN1") (pin "7") (pinfunction "7_7") (pintype "passive"))
    )
    (net (code "57") (name "unconnected-(CN1-Pad8)") (class "Default")
      (node (ref "CN1") (pin "8") (pinfunction "8_8") (pintype "passive"))
    )
    (net (code "58") (name "unconnected-(M1-Pad1)") (class "Default")
      (node (ref "M1") (pin "1") (pinfunction "1_1") (pintype "passive"))
    )
    (net (code "59") (name "unconnected-(M2-Pad1)") (class "Default")
      (node (ref "M2") (pin "1") (pinfunction "1_1") (pintype "passive"))
    )
    (net (code "60") (name "unconnected-(M3-Pad1)") (class "Default")
      (node (ref "M3") (pin "1") (pinfunction "1_1") (pintype "passive"))
    )
    (net (code "61") (name "unconnected-(TP22-Pad1)") (class "Default")
      (node (ref "TP22") (pin "1") (pinfunction "1_1") (pintype "passive"))
    )
    (net (code "62") (name "unconnected-(TP23-Pad1)") (class "Default")
      (node (ref "TP23") (pin "1") (pinfunction "1_1") (pintype "passive"))
    )
    (net (code "63") (name "unconnected-(U2-PA0-WKUP-Pad10)") (class "Default")
      (node (ref "U2") (pin "10") (pinfunction "PA0-WKUP_10") (pintype "bidirectional"))
    )
    (net (code "64") (name "unconnected-(U2-PA6-Pad16)") (class "Default")
      (node (ref "U2") (pin "16") (pinfunction "PA6_16") (pintype "bidirectional"))
    )
    (net (code "65") (name "unconnected-(U2-PA15-Pad38)") (class "Default")
      (node (ref "U2") (pin "38") (pinfunction "PA15_38") (pintype "bidirectional"))
    )
    (net (code "66") (name "unconnected-(U2-PB5-Pad41)") (class "Default")
      (node (ref "U2") (pin "41") (pinfunction "PB5_41") (pintype "bidirectional"))
    )
    (net (code "67") (name "unconnected-(U2-PB9-Pad46)") (class "Default")
      (node (ref "U2") (pin "46") (pinfunction "PB9_46") (pintype "bidirectional"))
    )
    (net (code "68") (name "unconnected-(U2-PB12-Pad25)") (class "Default")
      (node (ref "U2") (pin "25") (pinfunction "PB12_25") (pintype "bidirectional"))
    )
    (net (code "69") (name "unconnected-(U2-PB13-Pad26)") (class "Default")
      (node (ref "U2") (pin "26") (pinfunction "PB13_26") (pintype "bidirectional"))
    )
    (net (code "70") (name "unconnected-(U2-PB14-Pad27)") (class "Default")
      (node (ref "U2") (pin "27") (pinfunction "PB14_27") (pintype "bidirectional"))
    )
    (net (code "71") (name "unconnected-(U2-PC13-TAMPER-RTC-Pad2)") (class "Default")
      (node (ref "U2") (pin "2") (pinfunction "PC13-TAMPER-RTC_2") (pintype "bidirectional"))
    )
    (net (code "72") (name "unconnected-(U2-PC14-OSC32_IN-Pad3)") (class "Default")
      (node (ref "U2") (pin "3") (pinfunction "PC14-OSC32_IN_3") (pintype "bidirectional"))
    )
    (net (code "73") (name "unconnected-(U2-PC15-OSC32_OUT-Pad4)") (class "Default")
      (node (ref "U2") (pin "4") (pinfunction "PC15-OSC32_OUT_4") (pintype "bidirectional"))
    )
    (net (code "74") (name "unconnected-(U7-EN-Pad5)") (class "Default")
      (node (ref "U7") (pin "5") (pinfunction "EN_5") (pintype "input+no_connect"))
    )
    (net (code "75") (name "unconnected-(U7-RS-Pad8)") (class "Default")
      (node (ref "U7") (pin "8") (pinfunction "RS_8") (pintype "input+no_connect"))
    )
  )
)
